# FrontPanel.net
KiCad netlist of a schematic drawn in EAGLE
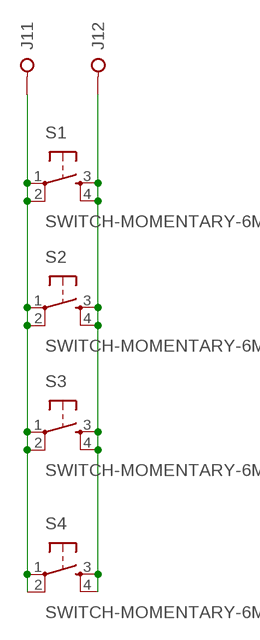
[diagram p0: schematic, sheet 1]

(export (version "E")
  (design (tool "Eeschema 10.0.6"))
  (components
    (comp (ref "J1")
      (value "PINHD-1X2BIG")
      (footprint "eagle-import:1X02-BIG")
      (libsource (lib "eagle-import") (part "PINHD-1X2BIG"))
    )
    (comp (ref "S1")
      (value "SWITCH-MOMENTARY-6MM")
      (footprint "eagle-import:TACTILE-SWITCH-6MM")
      (libsource (lib "eagle-import") (part "SWITCH-MOMENTARY-6MM"))
    )
    (comp (ref "S2")
      (value "SWITCH-MOMENTARY-6MM")
      (footprint "eagle-import:TACTILE-SWITCH-6MM")
      (libsource (lib "eagle-import") (part "SWITCH-MOMENTARY-6MM"))
    )
    (comp (ref "S3")
      (value "SWITCH-MOMENTARY-6MM")
      (footprint "eagle-import:TACTILE-SWITCH-6MM")
      (libsource (lib "eagle-import") (part "SWITCH-MOMENTARY-6MM"))
    )
    (comp (ref "S4")
      (value "SWITCH-MOMENTARY-6MM")
      (footprint "eagle-import:TACTILE-SWITCH-6MM")
      (libsource (lib "eagle-import") (part "SWITCH-MOMENTARY-6MM"))
    )
  )
  (nets
    (net (code "1") (name "Net-(J1A-KL)") (class "Default")
      (node (ref "J1") (pin "1") (pinfunction "KL_1") (pintype "passive"))
      (node (ref "S1") (pin "1") (pinfunction "1_1") (pintype "passive"))
      (node (ref "S1") (pin "2") (pinfunction "2_2") (pintype "passive"))
      (node (ref "S2") (pin "1") (pinfunction "1_1") (pintype "passive"))
      (node (ref "S2") (pin "2") (pinfunction "2_2") (pintype "passive"))
      (node (ref "S3") (pin "1") (pinfunction "1_1") (pintype "passive"))
      (node (ref "S3") (pin "2") (pinfunction "2_2") (pintype "passive"))
      (node (ref "S4") (pin "1") (pinfunction "1_1") (pintype "passive"))
      (node (ref "S4") (pin "2") (pinfunction "2_2") (pintype "passive"))
    )
    (net (code "2") (name "Net-(J1B-KL)") (class "Default")
      (node (ref "J1") (pin "2") (pinfunction "KL_2") (pintype "passive"))
      (node (ref "S1") (pin "3") (pinfunction "3_3") (pintype "passive"))
      (node (ref "S1") (pin "4") (pinfunction "4_4") (pintype "passive"))
      (node (ref "S2") (pin "3") (pinfunction "3_3") (pintype "passive"))
      (node (ref "S2") (pin "4") (pinfunction "4_4") (pintype "passive"))
      (node (ref "S3") (pin "3") (pinfunction "3_3") (pintype "passive"))
      (node (ref "S3") (pin "4") (pinfunction "4_4") (pintype "passive"))
      (node (ref "S4") (pin "3") (pinfunction "3_3") (pintype "passive"))
      (node (ref "S4") (pin "4") (pinfunction "4_4") (pintype "passive"))
    )
  )
)
